# Dual_handheld_laser_sword_2_0.net
KiCad netlist of a schematic drawn in EasyEDA Pro
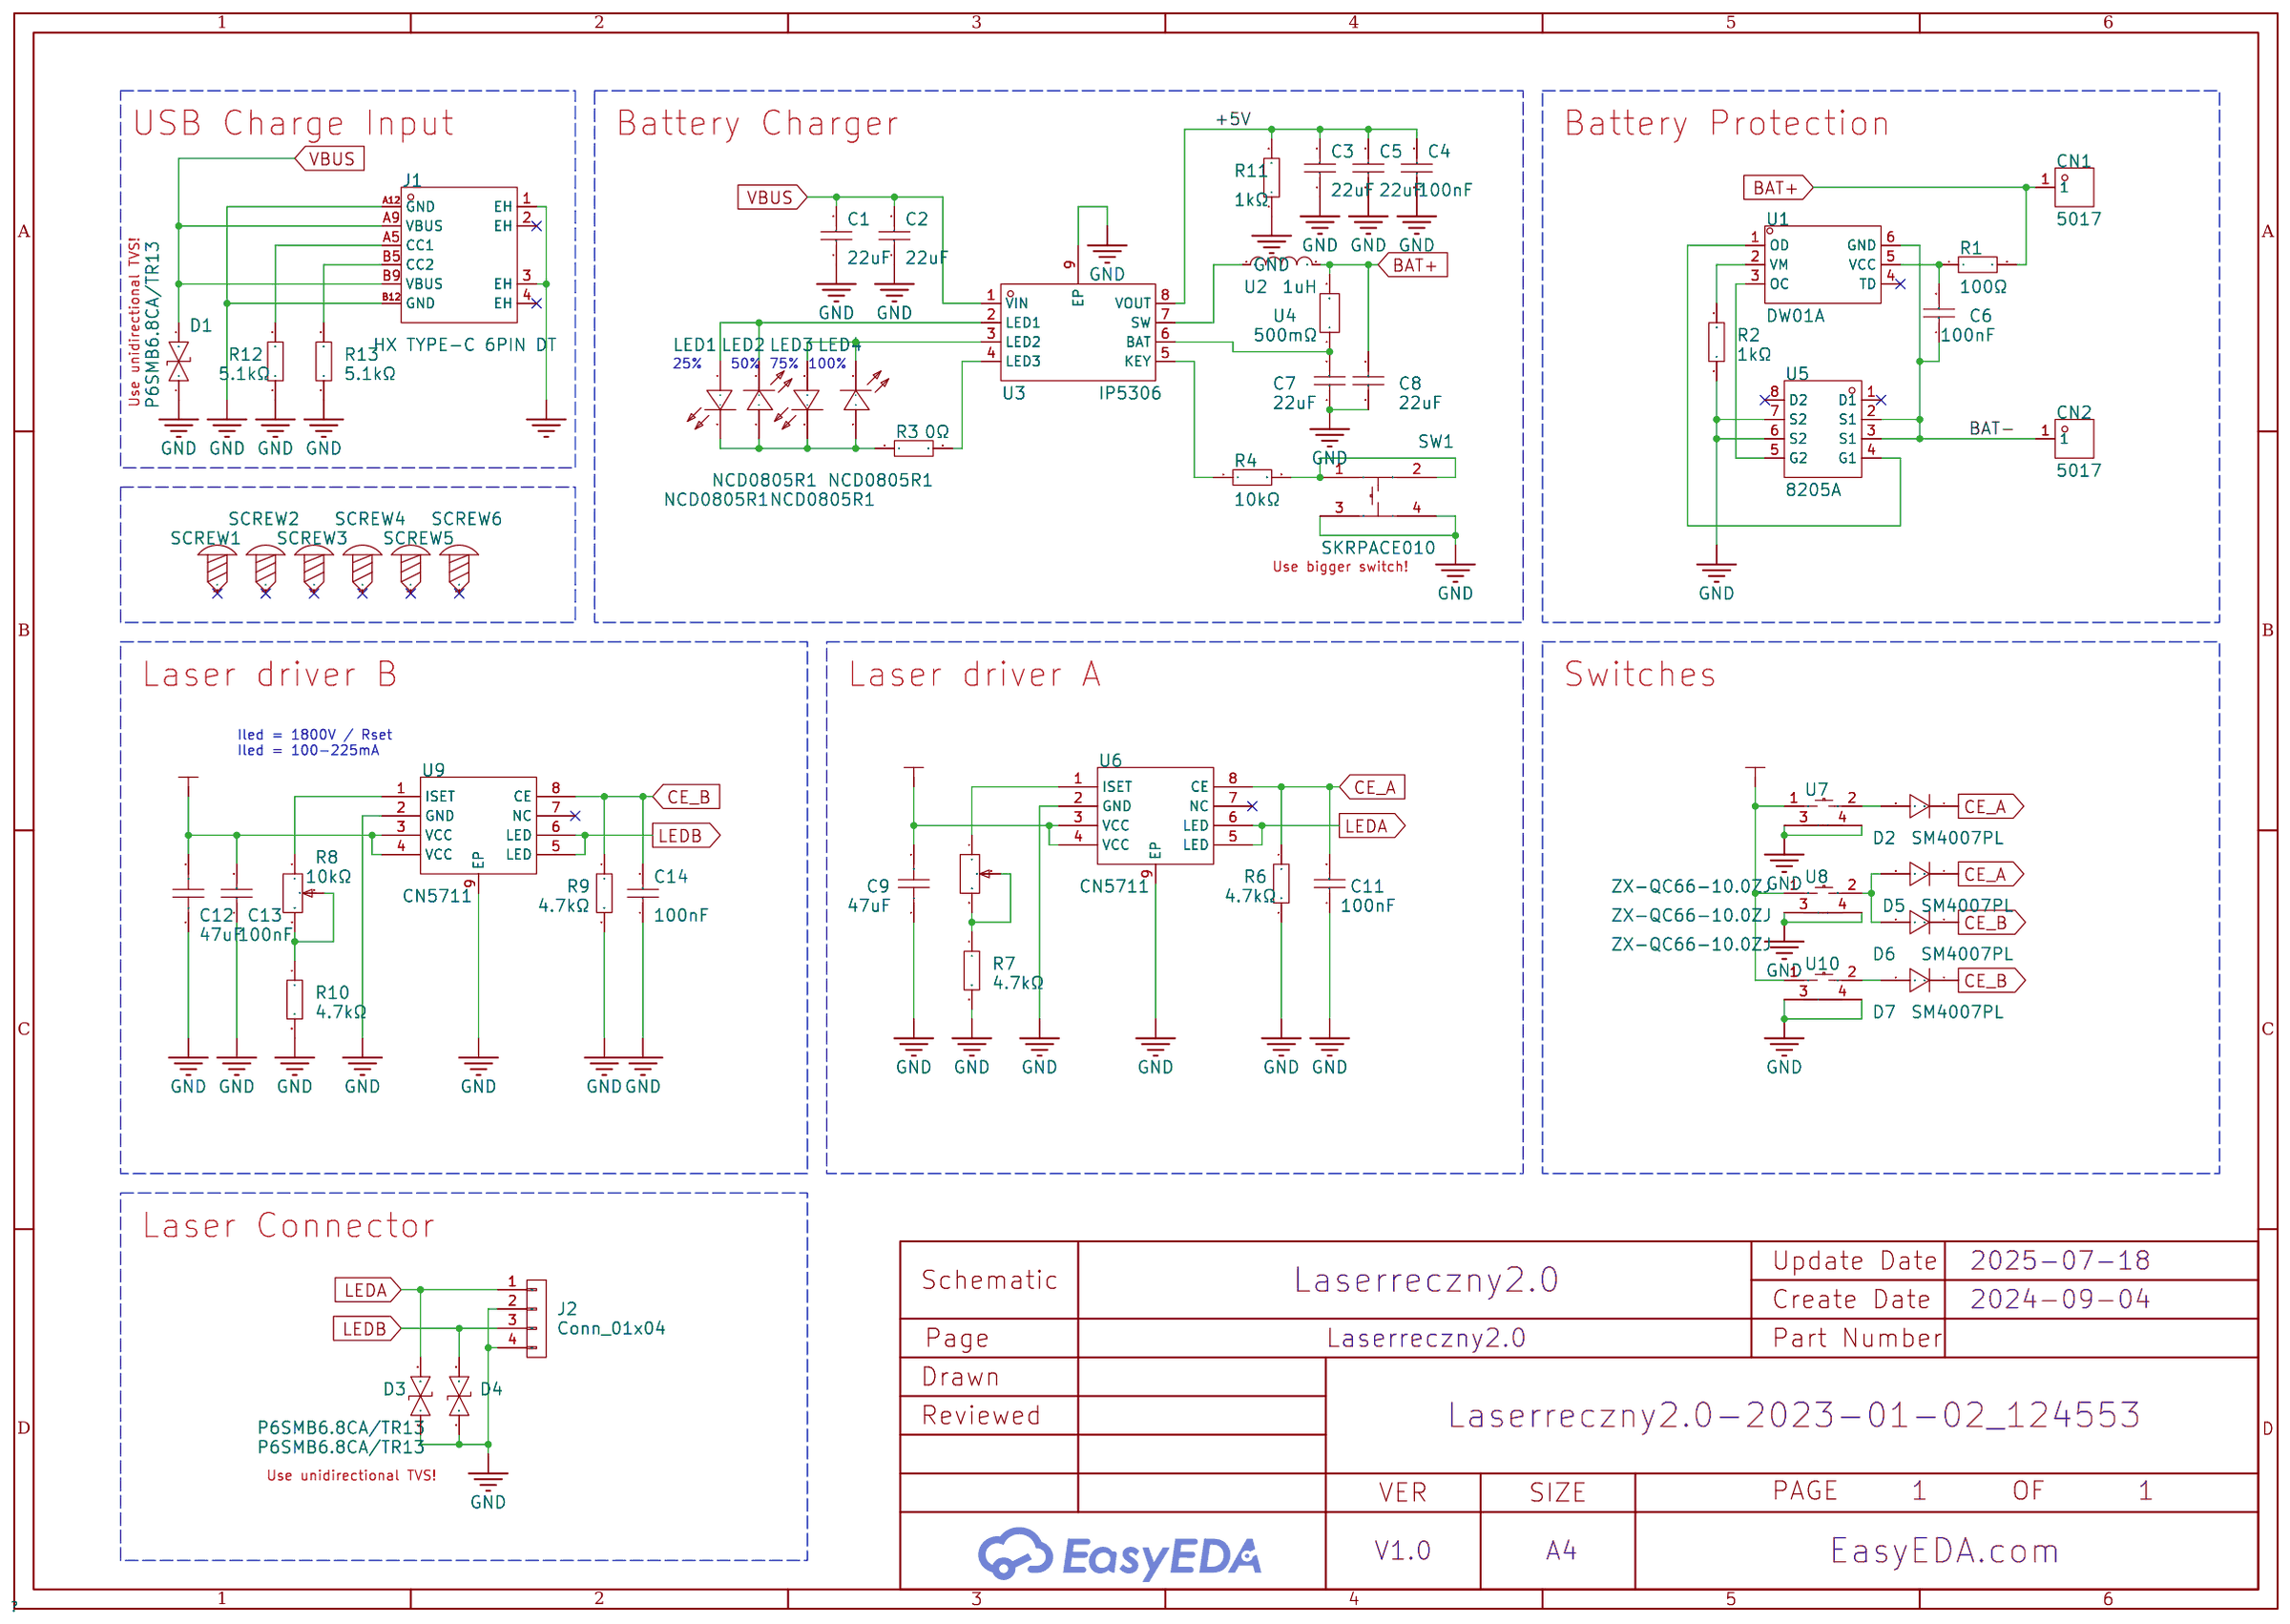
[diagram p0: schematic sheet]

(export (version "E")
  (design (tool "Eeschema 10.0.6"))
  (components
    (comp (ref "C1")
      (value "22uF")
      (footprint "easyedapro:C1206")
      (fields
        (field (name "Manufacturer Part") "CL31A226KAHNNNE")
        (field (name "Manufacturer") "SAMSUNG(三星)")
      )
      (libsource (lib "easyedapro") (part "CL31A226KAHNNNE"))
    )
    (comp (ref "C2")
      (value "22uF")
      (footprint "easyedapro:C1206")
      (fields
        (field (name "Manufacturer Part") "CL31A226KAHNNNE")
        (field (name "Manufacturer") "SAMSUNG(三星)")
      )
      (libsource (lib "easyedapro") (part "CL31A226KAHNNNE"))
    )
    (comp (ref "C3")
      (value "22uF")
      (footprint "easyedapro:C1206")
      (fields
        (field (name "Manufacturer Part") "CL31A226KAHNNNE")
        (field (name "Manufacturer") "SAMSUNG(三星)")
      )
      (libsource (lib "easyedapro") (part "CL31A226KAHNNNE"))
    )
    (comp (ref "C4")
      (value "22uF")
      (footprint "easyedapro:C1206")
      (fields
        (field (name "Manufacturer Part") "CL31A226KAHNNNE")
        (field (name "Manufacturer") "SAMSUNG(三星)")
      )
      (libsource (lib "easyedapro") (part "CL31A226KAHNNNE"))
    )
    (comp (ref "C5")
      (value "100nF")
      (footprint "easyedapro:C1206")
      (fields
        (field (name "Manufacturer Part") "CL31B104KBCNNNC")
        (field (name "Manufacturer") "SAMSUNG(三星)")
      )
      (libsource (lib "easyedapro") (part "CL31B104KBCNNNC"))
    )
    (comp (ref "C6")
      (value "100nF")
      (footprint "easyedapro:C1206")
      (fields
        (field (name "Manufacturer Part") "CL31B104KBCNNNC")
        (field (name "Manufacturer") "SAMSUNG(三星)")
      )
      (libsource (lib "easyedapro") (part "CL31B104KBCNNNC"))
    )
    (comp (ref "C7")
      (value "22uF")
      (footprint "easyedapro:C1206")
      (fields
        (field (name "Manufacturer Part") "CL31A226KAHNNNE")
        (field (name "Manufacturer") "SAMSUNG(三星)")
      )
      (libsource (lib "easyedapro") (part "CL31A226KAHNNNE"))
    )
    (comp (ref "C8")
      (value "22uF")
      (footprint "easyedapro:C1206")
      (fields
        (field (name "Manufacturer Part") "CL31A226KAHNNNE")
        (field (name "Manufacturer") "SAMSUNG(三星)")
      )
      (libsource (lib "easyedapro") (part "CL31A226KAHNNNE"))
    )
    (comp (ref "C9")
      (value "47uF")
      (footprint "easyedapro:C1206")
      (fields
        (field (name "Manufacturer Part") "CL31A476MPHNNNE")
        (field (name "Manufacturer") "SAMSUNG(三星)")
      )
      (libsource (lib "easyedapro") (part "CL31A476MPHNNNE"))
    )
    (comp (ref "C11")
      (value "100nF")
      (footprint "easyedapro:C1206")
      (fields
        (field (name "Manufacturer Part") "CL31B104KBCNNNC")
        (field (name "Manufacturer") "SAMSUNG(三星)")
      )
      (libsource (lib "easyedapro") (part "CL31B104KBCNNNC"))
    )
    (comp (ref "C12")
      (value "47uF")
      (footprint "easyedapro:C1206")
      (fields
        (field (name "Manufacturer Part") "CL31A476MPHNNNE")
        (field (name "Manufacturer") "SAMSUNG(三星)")
      )
      (libsource (lib "easyedapro") (part "CL31A476MPHNNNE"))
    )
    (comp (ref "C13")
      (value "100nF")
      (footprint "easyedapro:C1206")
      (fields
        (field (name "Manufacturer Part") "CL31B104KBCNNNC")
        (field (name "Manufacturer") "SAMSUNG(三星)")
      )
      (libsource (lib "easyedapro") (part "CL31B104KBCNNNC"))
    )
    (comp (ref "C14")
      (value "100nF")
      (footprint "easyedapro:C1206")
      (fields
        (field (name "Manufacturer Part") "CL31B104KBCNNNC")
        (field (name "Manufacturer") "SAMSUNG(三星)")
      )
      (libsource (lib "easyedapro") (part "CL31B104KBCNNNC"))
    )
    (comp (ref "CN1")
      (value "5017")
      (footprint "easyedapro:CONN-SMD_5017")
      (libsource (lib "easyedapro") (part "5017_C9900015874"))
    )
    (comp (ref "CN2")
      (value "5017")
      (footprint "easyedapro:CONN-SMD_5017")
      (libsource (lib "easyedapro") (part "5017_C9900015874"))
    )
    (comp (ref "D1")
      (value "P6SMB6.8CA/TR13")
      (footprint "easyedapro:SMB_L4.6-W3.6-LS5.3-BI")
      (fields (field (name "Manufacturer") "Brightking(君耀电子)"))
      (libsource (lib "easyedapro") (part "P6SMB6.8CA-C78395"))
    )
    (comp (ref "D2")
      (value "SM4007PL")
      (footprint "easyedapro:SOD-123F_L2.8-W1.8-LS3.7-RD")
      (fields (field (name "Manufacturer") "MDD(辰达半导体)"))
      (libsource (lib "easyedapro") (part "SM4007PL"))
    )
    (comp (ref "D3")
      (value "P6SMB6.8CA/TR13")
      (footprint "easyedapro:SMB_L4.6-W3.6-LS5.3-BI")
      (fields (field (name "Manufacturer") "Brightking(君耀电子)"))
      (libsource (lib "easyedapro") (part "P6SMB6.8CA-C78395"))
    )
    (comp (ref "D4")
      (value "P6SMB6.8CA/TR13")
      (footprint "easyedapro:SMB_L4.6-W3.6-LS5.3-BI")
      (fields (field (name "Manufacturer") "Brightking(君耀电子)"))
      (libsource (lib "easyedapro") (part "P6SMB6.8CA-C78395"))
    )
    (comp (ref "D5")
      (value "SM4007PL")
      (footprint "easyedapro:SOD-123F_L2.8-W1.8-LS3.7-RD")
      (fields (field (name "Manufacturer") "MDD(辰达半导体)"))
      (libsource (lib "easyedapro") (part "SM4007PL"))
    )
    (comp (ref "D6")
      (value "SM4007PL")
      (footprint "easyedapro:SOD-123F_L2.8-W1.8-LS3.7-RD")
      (fields (field (name "Manufacturer") "MDD(辰达半导体)"))
      (libsource (lib "easyedapro") (part "SM4007PL"))
    )
    (comp (ref "D7")
      (value "SM4007PL")
      (footprint "easyedapro:SOD-123F_L2.8-W1.8-LS3.7-RD")
      (fields (field (name "Manufacturer") "MDD(辰达半导体)"))
      (libsource (lib "easyedapro") (part "SM4007PL"))
    )
    (comp (ref "J1")
      (value "HX TYPE-C 6PIN DT")
      (footprint "easyedapro:TYPE-C-SMD_TYPE-C-31-M-16")
      (fields (field (name "Manufacturer") "hanxia(韩下)"))
      (libsource (lib "easyedapro") (part "HX TYPE-C 6PIN DT"))
    )
    (comp (ref "J2")
      (value "Conn_01x04")
      (footprint "easyedapro:Nowy folder:UCHWYTLASERA3")
      (libsource (lib "easyedapro") (part "New_Library2_Conn_01x04"))
    )
    (comp (ref "LED1")
      (value "NCD0805R1")
      (footprint "easyedapro:LED0805-R-RD")
      (fields (field (name "Manufacturer") "国星光电"))
      (libsource (lib "easyedapro") (part "FC-2012HRK-620D"))
    )
    (comp (ref "LED2")
      (value "NCD0805R1")
      (footprint "easyedapro:LED0805-R-RD")
      (fields (field (name "Manufacturer") "国星光电"))
      (libsource (lib "easyedapro") (part "FC-2012HRK-620D"))
    )
    (comp (ref "LED3")
      (value "NCD0805R1")
      (footprint "easyedapro:LED0805-R-RD")
      (fields (field (name "Manufacturer") "国星光电"))
      (libsource (lib "easyedapro") (part "FC-2012HRK-620D"))
    )
    (comp (ref "LED4")
      (value "NCD0805R1")
      (footprint "easyedapro:LED0805-R-RD")
      (fields (field (name "Manufacturer") "国星光电"))
      (libsource (lib "easyedapro") (part "FC-2012HRK-620D"))
    )
    (comp (ref "R1")
      (value "100Ω")
      (footprint "easyedapro:R0805")
      (fields
        (field (name "Manufacturer Part") "0805W8F1000T5E")
        (field (name "Manufacturer") "UNI-ROYAL(厚声)")
      )
      (libsource (lib "easyedapro") (part "0805W8F1000T5E"))
    )
    (comp (ref "R2")
      (value "1kΩ")
      (footprint "easyedapro:R0805")
      (fields
        (field (name "Manufacturer Part") "0805W8F1001T5E")
        (field (name "Manufacturer") "UNI-ROYAL(厚声)")
      )
      (libsource (lib "easyedapro") (part "0805W8F1001T5E"))
    )
    (comp (ref "R3")
      (value "0Ω")
      (footprint "easyedapro:R1206")
      (fields
        (field (name "Manufacturer Part") "1206W4F0000T5E")
        (field (name "Manufacturer") "UNI-ROYAL(厚声)")
      )
      (libsource (lib "easyedapro") (part "1206W4F0000T5E"))
    )
    (comp (ref "R4")
      (value "10kΩ")
      (footprint "easyedapro:R1206")
      (fields
        (field (name "Manufacturer Part") "1206W4F1002T5E")
        (field (name "Manufacturer") "UNI-ROYAL(厚声)")
      )
      (libsource (lib "easyedapro") (part "1206W4F1002T5E"))
    )
    (comp (ref "R5")
      (value "10kΩ")
      (footprint "easyedapro:RES-ADJ-TH_3296W")
      (fields (field (name "Manufacturer Part") "3296W-1-103LF") (field (name "Manufacturer") "BOURNS"))
      (libsource (lib "easyedapro") (part "3296W-1-103LF"))
    )
    (comp (ref "R6")
      (value "4.7kΩ")
      (footprint "easyedapro:R1206")
      (fields
        (field (name "Manufacturer Part") "1206W4F4701T5E")
        (field (name "Manufacturer") "UNI-ROYAL(厚声)")
      )
      (libsource (lib "easyedapro") (part "1206W4F4701T5E"))
    )
    (comp (ref "R7")
      (value "4.7kΩ")
      (footprint "easyedapro:R1206")
      (fields
        (field (name "Manufacturer Part") "1206W4F4701T5E")
        (field (name "Manufacturer") "UNI-ROYAL(厚声)")
      )
      (libsource (lib "easyedapro") (part "1206W4F4701T5E"))
    )
    (comp (ref "R8")
      (value "10kΩ")
      (footprint "easyedapro:RES-ADJ-TH_3296W")
      (fields (field (name "Manufacturer Part") "3296W-1-103LF") (field (name "Manufacturer") "BOURNS"))
      (libsource (lib "easyedapro") (part "3296W-1-103LF"))
    )
    (comp (ref "R9")
      (value "4.7kΩ")
      (footprint "easyedapro:R1206")
      (fields
        (field (name "Manufacturer Part") "1206W4F4701T5E")
        (field (name "Manufacturer") "UNI-ROYAL(厚声)")
      )
      (libsource (lib "easyedapro") (part "1206W4F4701T5E"))
    )
    (comp (ref "R10")
      (value "4.7kΩ")
      (footprint "easyedapro:R1206")
      (fields
        (field (name "Manufacturer Part") "1206W4F4701T5E")
        (field (name "Manufacturer") "UNI-ROYAL(厚声)")
      )
      (libsource (lib "easyedapro") (part "1206W4F4701T5E"))
    )
    (comp (ref "R11")
      (value "1kΩ")
      (footprint "easyedapro:R0805")
      (fields
        (field (name "Manufacturer Part") "0805W8F1001T5E")
        (field (name "Manufacturer") "UNI-ROYAL(厚声)")
      )
      (libsource (lib "easyedapro") (part "0805W8F1001T5E"))
    )
    (comp (ref "R12")
      (value "5.1kΩ")
      (footprint "easyedapro:R0805")
      (fields (field (name "Manufacturer Part") "RMC08055.1K5%N") (field (name "Manufacturer") "Tyohm(幸亚电阻)"))
      (libsource (lib "easyedapro") (part "RMC08055.1K5%N"))
    )
    (comp (ref "R13")
      (value "5.1kΩ")
      (footprint "easyedapro:R0805")
      (fields (field (name "Manufacturer Part") "RMC08055.1K5%N") (field (name "Manufacturer") "Tyohm(幸亚电阻)"))
      (libsource (lib "easyedapro") (part "RMC08055.1K5%N"))
    )
    (comp (ref "SCREW1")
      (value "~")
      (footprint "easyedapro:Screw-Hole-M2")
      (libsource (lib "easyedapro") (part "Screw-Hole"))
    )
    (comp (ref "SCREW2")
      (value "~")
      (footprint "easyedapro:Screw-Hole-M2")
      (libsource (lib "easyedapro") (part "Screw-Hole"))
    )
    (comp (ref "SCREW3")
      (value "~")
      (footprint "easyedapro:Screw-Hole-M2")
      (libsource (lib "easyedapro") (part "Screw-Hole"))
    )
    (comp (ref "SCREW4")
      (value "~")
      (footprint "easyedapro:Screw-Hole-M2")
      (libsource (lib "easyedapro") (part "Screw-Hole"))
    )
    (comp (ref "SCREW5")
      (value "~")
      (footprint "easyedapro:Screw-Hole-M2")
      (libsource (lib "easyedapro") (part "Screw-Hole"))
    )
    (comp (ref "SCREW6")
      (value "~")
      (footprint "easyedapro:Screw-Hole-M2")
      (libsource (lib "easyedapro") (part "Screw-Hole"))
    )
    (comp (ref "SW1")
      (value "SKRPACE010")
      (footprint "easyedapro:KEY-SMD_4P-L4.2-W3.2-P2.20-LS4.6")
      (fields (field (name "Manufacturer") "ALPSALPINE(阿尔卑斯阿尔派)"))
      (libsource (lib "easyedapro") (part "SKRPACE010"))
    )
    (comp (ref "U1")
      (value "DW01A")
      (footprint "easyedapro:SOT-23-6_L2.9-W1.6-P0.95-LS2.8-BL")
      (fields (field (name "Manufacturer") "PUOLOP(迪浦)"))
      (libsource (lib "easyedapro") (part "DW01A_C351410"))
    )
    (comp (ref "U2")
      (value "1uH")
      (footprint "easyedapro:IND-SMD_L11.5-W10.0")
      (fields (field (name "Manufacturer Part") "FXL1050-1R0-M") (field (name "Manufacturer") "cjiang(长江微电)"))
      (libsource (lib "easyedapro") (part "FXL1050-1R0-M"))
    )
    (comp (ref "U3")
      (value "IP5306")
      (footprint "easyedapro:ESOP-8_L4.9-W3.9-P1.27-LS6.0-BL-EP")
      (fields (field (name "Manufacturer") "INJOINIC(英集芯)"))
      (libsource (lib "easyedapro") (part "IP5306"))
    )
    (comp (ref "U4")
      (value "500mΩ")
      (footprint "easyedapro:R0603")
      (fields (field (name "Manufacturer Part") "FRL0603JR500TS") (field (name "Manufacturer") "FOJAN(富捷)"))
      (libsource (lib "easyedapro") (part "FRL0603JR500TS"))
    )
    (comp (ref "U5")
      (value "8205A")
      (footprint "easyedapro:TSSOP-8_L4.4-W3.0-P0.65-LS6.4-BL")
      (fields (field (name "Manufacturer") "HL(富海微)"))
      (libsource (lib "easyedapro") (part "8205A_C7499846"))
    )
    (comp (ref "U6")
      (value "CN5711")
      (footprint "easyedapro:SOIC-8_L5.0-W4.0-P1.27-LS6.0-BL-EP2.0")
      (fields (field (name "Manufacturer") "CONSONANCE(上海如韵)"))
      (libsource (lib "easyedapro") (part "CN5711"))
    )
    (comp (ref "U7")
      (value "ZX-QC66-10.0ZJ")
      (footprint "easyedapro:SW-TH_4P-L7.5-W5.5-P4.50")
      (fields (field (name "Manufacturer") "Megastar(兆星)"))
      (libsource (lib "easyedapro") (part "ZX-QC66-10.0ZJ"))
    )
    (comp (ref "U8")
      (value "ZX-QC66-10.0ZJ")
      (footprint "easyedapro:SW-TH_4P-L7.5-W5.5-P4.50")
      (fields (field (name "Manufacturer") "Megastar(兆星)"))
      (libsource (lib "easyedapro") (part "ZX-QC66-10.0ZJ"))
    )
    (comp (ref "U9")
      (value "CN5711")
      (footprint "easyedapro:SOIC-8_L5.0-W4.0-P1.27-LS6.0-BL-EP2.0")
      (fields (field (name "Manufacturer") "CONSONANCE(上海如韵)"))
      (libsource (lib "easyedapro") (part "CN5711"))
    )
    (comp (ref "U10")
      (value "ZX-QC66-10.0ZJ")
      (footprint "easyedapro:SW-TH_4P-L7.5-W5.5-P4.50")
      (fields (field (name "Manufacturer") "Megastar(兆星)"))
      (libsource (lib "easyedapro") (part "ZX-QC66-10.0ZJ"))
    )
  )
  (nets
    (net (code "1") (name "/+5V") (class "Default")
      (node (ref "C3") (pin "2") (pinfunction "2_2") (pintype "input"))
      (node (ref "C4") (pin "2") (pinfunction "2_2") (pintype "input"))
      (node (ref "C5") (pin "2") (pinfunction "2_2") (pintype "input"))
      (node (ref "R11") (pin "2") (pinfunction "2_2") (pintype "input"))
      (node (ref "U3") (pin "8") (pinfunction "VOUT_8") (pintype "unspecified"))
    )
    (net (code "2") (name "BAT+") (class "Default")
      (node (ref "C12") (pin "2") (pinfunction "2_2") (pintype "unspecified"))
      (node (ref "C13") (pin "2") (pinfunction "2_2") (pintype "input"))
      (node (ref "C8") (pin "2") (pinfunction "2_2") (pintype "input"))
      (node (ref "C9") (pin "2") (pinfunction "2_2") (pintype "unspecified"))
      (node (ref "CN1") (pin "1") (pinfunction "1_1") (pintype "unspecified"))
      (node (ref "R1") (pin "2") (pinfunction "2_2") (pintype "input"))
      (node (ref "U10") (pin "1") (pinfunction "1_1") (pintype "unspecified"))
      (node (ref "U2") (pin "2") (pinfunction "2_2") (pintype "unspecified"))
      (node (ref "U4") (pin "2") (pinfunction "2_2") (pintype "unspecified"))
      (node (ref "U6") (pin "3") (pinfunction "VCC_3") (pintype "input"))
      (node (ref "U6") (pin "4") (pinfunction "VCC_4") (pintype "input"))
      (node (ref "U7") (pin "1") (pinfunction "1_1") (pintype "unspecified"))
      (node (ref "U8") (pin "1") (pinfunction "1_1") (pintype "unspecified"))
      (node (ref "U9") (pin "3") (pinfunction "VCC_3") (pintype "input"))
      (node (ref "U9") (pin "4") (pinfunction "VCC_4") (pintype "input"))
    )
    (net (code "3") (name "BAT-") (class "Default")
      (node (ref "C6") (pin "1") (pinfunction "1_1") (pintype "input"))
      (node (ref "CN2") (pin "1") (pinfunction "1_1") (pintype "unspecified"))
      (node (ref "J1") (pin "1") (pinfunction "EH_1") (pintype "unspecified"))
      (node (ref "J1") (pin "3") (pinfunction "EH_3") (pintype "unspecified"))
      (node (ref "U1") (pin "6") (pinfunction "GND_6") (pintype "input"))
      (node (ref "U5") (pin "2") (pinfunction "S1_2") (pintype "unspecified"))
      (node (ref "U5") (pin "3") (pinfunction "S1_3") (pintype "unspecified"))
    )
    (net (code "4") (name "CE_A") (class "Default")
      (node (ref "C11") (pin "2") (pinfunction "2_2") (pintype "input"))
      (node (ref "D2") (pin "1") (pinfunction "C_1") (pintype "unspecified"))
      (node (ref "D5") (pin "1") (pinfunction "C_1") (pintype "unspecified"))
      (node (ref "R6") (pin "1") (pinfunction "1_1") (pintype "input"))
      (node (ref "U6") (pin "8") (pinfunction "CE_8") (pintype "input"))
    )
    (net (code "5") (name "CE_B") (class "Default")
      (node (ref "C14") (pin "2") (pinfunction "2_2") (pintype "input"))
      (node (ref "D6") (pin "1") (pinfunction "C_1") (pintype "unspecified"))
      (node (ref "D7") (pin "1") (pinfunction "C_1") (pintype "unspecified"))
      (node (ref "R9") (pin "1") (pinfunction "1_1") (pintype "input"))
      (node (ref "U9") (pin "8") (pinfunction "CE_8") (pintype "input"))
    )
    (net (code "6") (name "GND") (class "Default")
      (node (ref "C1") (pin "1") (pinfunction "1_1") (pintype "input"))
      (node (ref "C11") (pin "1") (pinfunction "1_1") (pintype "input"))
      (node (ref "C12") (pin "1") (pinfunction "1_1") (pintype "unspecified"))
      (node (ref "C13") (pin "1") (pinfunction "1_1") (pintype "input"))
      (node (ref "C14") (pin "1") (pinfunction "1_1") (pintype "input"))
      (node (ref "C2") (pin "1") (pinfunction "1_1") (pintype "input"))
      (node (ref "C3") (pin "1") (pinfunction "1_1") (pintype "input"))
      (node (ref "C4") (pin "1") (pinfunction "1_1") (pintype "input"))
      (node (ref "C5") (pin "1") (pinfunction "1_1") (pintype "input"))
      (node (ref "C7") (pin "1") (pinfunction "1_1") (pintype "input"))
      (node (ref "C8") (pin "1") (pinfunction "1_1") (pintype "input"))
      (node (ref "C9") (pin "1") (pinfunction "1_1") (pintype "unspecified"))
      (node (ref "D1") (pin "1") (pinfunction "1_1") (pintype "unspecified"))
      (node (ref "D3") (pin "1") (pinfunction "1_1") (pintype "unspecified"))
      (node (ref "D4") (pin "1") (pinfunction "1_1") (pintype "unspecified"))
      (node (ref "J1") (pin "A12") (pinfunction "GND_A12") (pintype "unspecified"))
      (node (ref "J1") (pin "B12") (pinfunction "GND_B12") (pintype "unspecified"))
      (node (ref "J2") (pin "2") (pinfunction "Pin_2_2") (pintype "unspecified"))
      (node (ref "J2") (pin "4") (pinfunction "Pin_4_4") (pintype "unspecified"))
      (node (ref "R10") (pin "2") (pinfunction "2_2") (pintype "input"))
      (node (ref "R11") (pin "1") (pinfunction "1_1") (pintype "input"))
      (node (ref "R12") (pin "1") (pinfunction "1_1") (pintype "input"))
      (node (ref "R13") (pin "1") (pinfunction "1_1") (pintype "input"))
      (node (ref "R2") (pin "1") (pinfunction "1_1") (pintype "input"))
      (node (ref "R6") (pin "2") (pinfunction "2_2") (pintype "input"))
      (node (ref "R7") (pin "2") (pinfunction "2_2") (pintype "input"))
      (node (ref "R9") (pin "2") (pinfunction "2_2") (pintype "input"))
      (node (ref "SW1") (pin "3") (pinfunction "3_3") (pintype "input"))
      (node (ref "SW1") (pin "4") (pinfunction "4_4") (pintype "input"))
      (node (ref "U10") (pin "3") (pinfunction "3_3") (pintype "unspecified"))
      (node (ref "U10") (pin "4") (pinfunction "4_4") (pintype "unspecified"))
      (node (ref "U3") (pin "9") (pinfunction "EP_9") (pintype "unspecified"))
      (node (ref "U5") (pin "6") (pinfunction "S2_6") (pintype "unspecified"))
      (node (ref "U5") (pin "7") (pinfunction "S2_7") (pintype "unspecified"))
      (node (ref "U6") (pin "2") (pinfunction "GND_2") (pintype "input"))
      (node (ref "U6") (pin "9") (pinfunction "EP_9") (pintype "input"))
      (node (ref "U7") (pin "3") (pinfunction "3_3") (pintype "unspecified"))
      (node (ref "U7") (pin "4") (pinfunction "4_4") (pintype "unspecified"))
      (node (ref "U8") (pin "3") (pinfunction "3_3") (pintype "unspecified"))
      (node (ref "U8") (pin "4") (pinfunction "4_4") (pintype "unspecified"))
      (node (ref "U9") (pin "2") (pinfunction "GND_2") (pintype "input"))
      (node (ref "U9") (pin "9") (pinfunction "EP_9") (pintype "input"))
    )
    (net (code "7") (name "LEDA") (class "Default")
      (node (ref "D3") (pin "2") (pinfunction "2_2") (pintype "unspecified"))
      (node (ref "J2") (pin "1") (pinfunction "Pin_1_1") (pintype "unspecified"))
      (node (ref "U6") (pin "5") (pinfunction "LED_5") (pintype "input"))
      (node (ref "U6") (pin "6") (pinfunction "LED_6") (pintype "input"))
    )
    (net (code "8") (name "LEDB") (class "Default")
      (node (ref "D4") (pin "2") (pinfunction "2_2") (pintype "unspecified"))
      (node (ref "J2") (pin "3") (pinfunction "Pin_3_3") (pintype "unspecified"))
      (node (ref "U9") (pin "5") (pinfunction "LED_5") (pintype "input"))
      (node (ref "U9") (pin "6") (pinfunction "LED_6") (pintype "input"))
    )
    (net (code "9") (name "Net-(D2-A)") (class "Default")
      (node (ref "D2") (pin "2") (pinfunction "A_2") (pintype "unspecified"))
      (node (ref "U7") (pin "2") (pinfunction "2_2") (pintype "unspecified"))
    )
    (net (code "10") (name "Net-(D5-A)") (class "Default")
      (node (ref "D5") (pin "2") (pinfunction "A_2") (pintype "unspecified"))
      (node (ref "D6") (pin "2") (pinfunction "A_2") (pintype "unspecified"))
      (node (ref "U8") (pin "2") (pinfunction "2_2") (pintype "unspecified"))
    )
    (net (code "11") (name "Net-(D7-A)") (class "Default")
      (node (ref "D7") (pin "2") (pinfunction "A_2") (pintype "unspecified"))
      (node (ref "U10") (pin "2") (pinfunction "2_2") (pintype "unspecified"))
    )
    (net (code "12") (name "Net-(J1-CC1)") (class "Default")
      (node (ref "J1") (pin "A5") (pinfunction "CC1_A5") (pintype "unspecified"))
      (node (ref "R12") (pin "2") (pinfunction "2_2") (pintype "input"))
    )
    (net (code "13") (name "Net-(J1-CC2)") (class "Default")
      (node (ref "J1") (pin "B5") (pinfunction "CC2_B5") (pintype "unspecified"))
      (node (ref "R13") (pin "2") (pinfunction "2_2") (pintype "input"))
    )
    (net (code "14") (name "Net-(LED1-+)") (class "Default")
      (node (ref "LED1") (pin "1") (pinfunction "+_1") (pintype "unspecified"))
      (node (ref "LED2") (pin "2") (pinfunction "-_2") (pintype "unspecified"))
      (node (ref "U3") (pin "2") (pinfunction "LED1_2") (pintype "unspecified"))
    )
    (net (code "15") (name "Net-(LED1--)") (class "Default")
      (node (ref "LED1") (pin "2") (pinfunction "-_2") (pintype "unspecified"))
      (node (ref "LED2") (pin "1") (pinfunction "+_1") (pintype "unspecified"))
      (node (ref "LED3") (pin "2") (pinfunction "-_2") (pintype "unspecified"))
      (node (ref "LED4") (pin "1") (pinfunction "+_1") (pintype "unspecified"))
      (node (ref "R3") (pin "1") (pinfunction "1_1") (pintype "input"))
    )
    (net (code "16") (name "Net-(LED3-+)") (class "Default")
      (node (ref "LED3") (pin "1") (pinfunction "+_1") (pintype "unspecified"))
      (node (ref "LED4") (pin "2") (pinfunction "-_2") (pintype "unspecified"))
      (node (ref "U3") (pin "3") (pinfunction "LED2_3") (pintype "unspecified"))
    )
    (net (code "17") (name "Net-(R4-Pad2)") (class "Default")
      (node (ref "R4") (pin "2") (pinfunction "2_2") (pintype "input"))
      (node (ref "SW1") (pin "1") (pinfunction "1_1") (pintype "input"))
      (node (ref "SW1") (pin "2") (pinfunction "2_2") (pintype "input"))
    )
    (net (code "18") (name "Net-(R5-Pad2)") (class "Default")
      (node (ref "R5") (pin "2") (pinfunction "2_2") (pintype "input"))
      (node (ref "R5") (pin "3") (pinfunction "3_3") (pintype "input"))
      (node (ref "R7") (pin "1") (pinfunction "1_1") (pintype "input"))
    )
    (net (code "19") (name "Net-(R10-Pad1)") (class "Default")
      (node (ref "R10") (pin "1") (pinfunction "1_1") (pintype "input"))
      (node (ref "R8") (pin "2") (pinfunction "2_2") (pintype "input"))
      (node (ref "R8") (pin "3") (pinfunction "3_3") (pintype "input"))
    )
    (net (code "20") (name "Net-(U1-OC)") (class "Default")
      (node (ref "U1") (pin "3") (pinfunction "OC_3") (pintype "input"))
      (node (ref "U5") (pin "5") (pinfunction "G2_5") (pintype "unspecified"))
    )
    (net (code "21") (name "Net-(U1-OD)") (class "Default")
      (node (ref "U1") (pin "1") (pinfunction "OD_1") (pintype "input"))
      (node (ref "U5") (pin "4") (pinfunction "G1_4") (pintype "unspecified"))
    )
    (net (code "22") (name "Net-(U1-VCC)") (class "Default")
      (node (ref "C6") (pin "2") (pinfunction "2_2") (pintype "input"))
      (node (ref "R1") (pin "1") (pinfunction "1_1") (pintype "input"))
      (node (ref "U1") (pin "5") (pinfunction "VCC_5") (pintype "input"))
    )
    (net (code "23") (name "Net-(U1-VM)") (class "Default")
      (node (ref "R2") (pin "2") (pinfunction "2_2") (pintype "input"))
      (node (ref "U1") (pin "2") (pinfunction "VM_2") (pintype "input"))
    )
    (net (code "24") (name "Net-(U3-BAT)") (class "Default")
      (node (ref "C7") (pin "2") (pinfunction "2_2") (pintype "input"))
      (node (ref "U3") (pin "6") (pinfunction "BAT_6") (pintype "unspecified"))
      (node (ref "U4") (pin "1") (pinfunction "1_1") (pintype "unspecified"))
    )
    (net (code "25") (name "Net-(U3-KEY)") (class "Default")
      (node (ref "R4") (pin "1") (pinfunction "1_1") (pintype "input"))
      (node (ref "U3") (pin "5") (pinfunction "KEY_5") (pintype "unspecified"))
    )
    (net (code "26") (name "Net-(U3-LED3)") (class "Default")
      (node (ref "R3") (pin "2") (pinfunction "2_2") (pintype "input"))
      (node (ref "U3") (pin "4") (pinfunction "LED3_4") (pintype "unspecified"))
    )
    (net (code "27") (name "Net-(U3-SW)") (class "Default")
      (node (ref "U2") (pin "1") (pinfunction "1_1") (pintype "unspecified"))
      (node (ref "U3") (pin "7") (pinfunction "SW_7") (pintype "unspecified"))
    )
    (net (code "28") (name "Net-(U6-ISET)") (class "Default")
      (node (ref "R5") (pin "1") (pinfunction "1_1") (pintype "input"))
      (node (ref "U6") (pin "1") (pinfunction "ISET_1") (pintype "input"))
    )
    (net (code "29") (name "Net-(U9-ISET)") (class "Default")
      (node (ref "R8") (pin "1") (pinfunction "1_1") (pintype "input"))
      (node (ref "U9") (pin "1") (pinfunction "ISET_1") (pintype "input"))
    )
    (net (code "30") (name "VBUS") (class "Default")
      (node (ref "C1") (pin "2") (pinfunction "2_2") (pintype "input"))
      (node (ref "C2") (pin "2") (pinfunction "2_2") (pintype "input"))
      (node (ref "D1") (pin "2") (pinfunction "2_2") (pintype "unspecified"))
      (node (ref "J1") (pin "A9") (pinfunction "VBUS_A9") (pintype "unspecified"))
      (node (ref "J1") (pin "B9") (pinfunction "VBUS_B9") (pintype "unspecified"))
      (node (ref "U3") (pin "1") (pinfunction "VIN_1") (pintype "unspecified"))
    )
    (net (code "31") (name "unconnected-(J1-EH-Pad2)") (class "Default")
      (node (ref "J1") (pin "2") (pinfunction "EH_2") (pintype "unspecified+no_connect"))
    )
    (net (code "32") (name "unconnected-(J1-EH-Pad4)") (class "Default")
      (node (ref "J1") (pin "4") (pinfunction "EH_4") (pintype "unspecified+no_connect"))
    )
    (net (code "33") (name "unconnected-(SCREW1-Pad1)") (class "Default")
      (node (ref "SCREW1") (pin "1") (pinfunction "1_1") (pintype "input+no_connect"))
    )
    (net (code "34") (name "unconnected-(SCREW2-Pad1)") (class "Default")
      (node (ref "SCREW2") (pin "1") (pinfunction "1_1") (pintype "input+no_connect"))
    )
    (net (code "35") (name "unconnected-(SCREW3-Pad1)") (class "Default")
      (node (ref "SCREW3") (pin "1") (pinfunction "1_1") (pintype "input+no_connect"))
    )
    (net (code "36") (name "unconnected-(SCREW4-Pad1)") (class "Default")
      (node (ref "SCREW4") (pin "1") (pinfunction "1_1") (pintype "input+no_connect"))
    )
    (net (code "37") (name "unconnected-(SCREW5-Pad1)") (class "Default")
      (node (ref "SCREW5") (pin "1") (pinfunction "1_1") (pintype "input+no_connect"))
    )
    (net (code "38") (name "unconnected-(SCREW6-Pad1)") (class "Default")
      (node (ref "SCREW6") (pin "1") (pinfunction "1_1") (pintype "input+no_connect"))
    )
    (net (code "39") (name "unconnected-(U1-TD-Pad4)") (class "Default")
      (node (ref "U1") (pin "4") (pinfunction "TD_4") (pintype "input+no_connect"))
    )
    (net (code "40") (name "unconnected-(U5-D1-Pad1)") (class "Default")
      (node (ref "U5") (pin "1") (pinfunction "D1_1") (pintype "unspecified+no_connect"))
    )
    (net (code "41") (name "unconnected-(U5-D2-Pad8)") (class "Default")
      (node (ref "U5") (pin "8") (pinfunction "D2_8") (pintype "unspecified+no_connect"))
    )
    (net (code "42") (name "unconnected-(U6-NC-Pad7)") (class "Default")
      (node (ref "U6") (pin "7") (pinfunction "NC_7") (pintype "input+no_connect"))
    )
    (net (code "43") (name "unconnected-(U9-NC-Pad7)") (class "Default")
      (node (ref "U9") (pin "7") (pinfunction "NC_7") (pintype "input+no_connect"))
    )
  )
)
